# Battery.net
KiCad netlist of a schematic drawn in Altium Designer
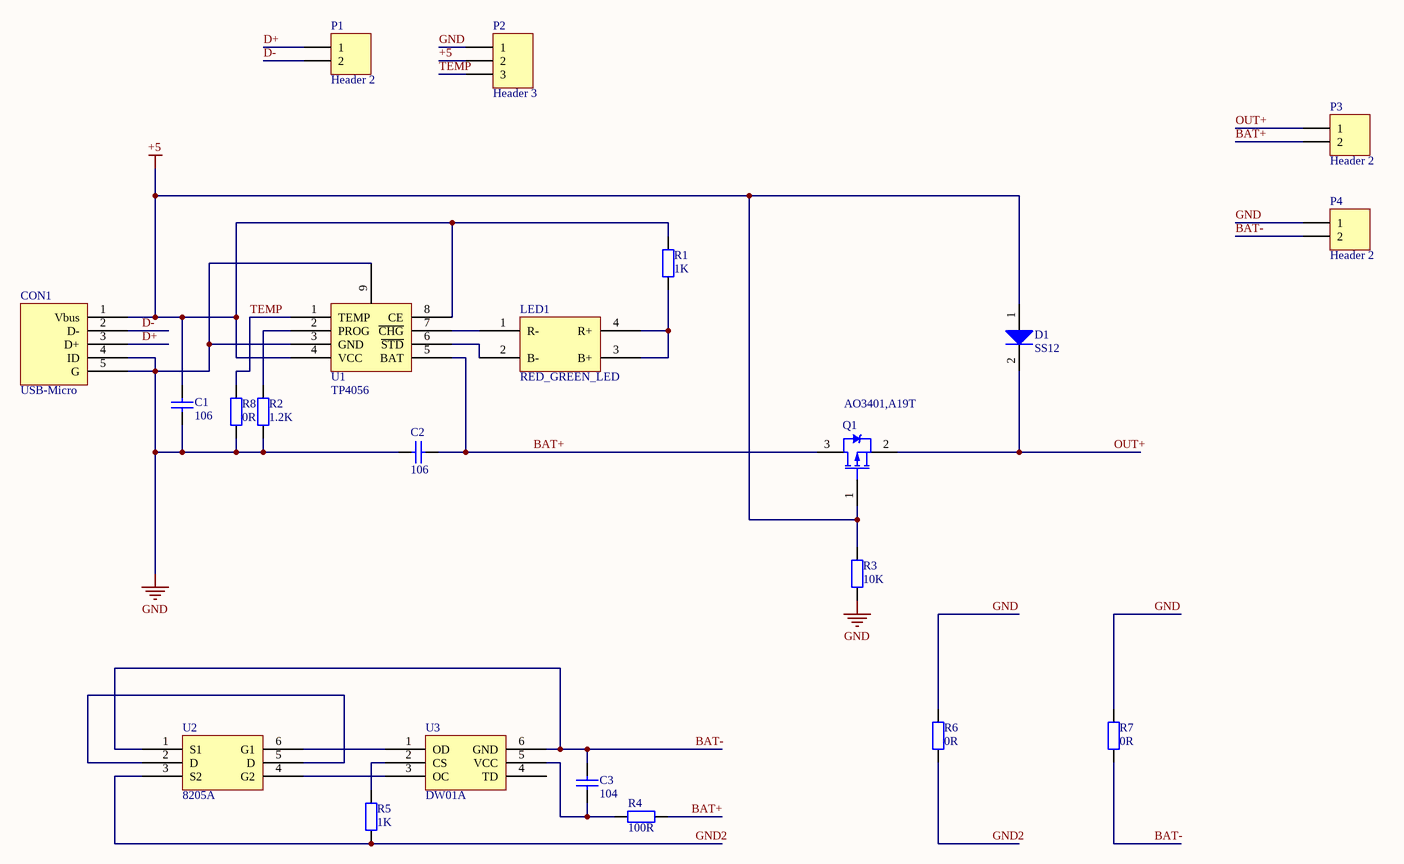
[diagram p0: Battery.SchDoc]

(export (version "E")
  (design (tool "Eeschema 10.0.6"))
  (components
    (comp (ref "C1")
      (value "106")
      (footprint "Battery:CAPC1608L")
      (description "Capacitor")
      (fields (field (name "Comment") "Cap") (field (name "PUBLISHER") "Altium Limited"))
      (libsource (lib "Miscellaneous Devices") (part "Cap"))
    )
    (comp (ref "C2")
      (value "106")
      (footprint "Battery:CAPC1608L")
      (description "Capacitor")
      (fields (field (name "Comment") "Cap") (field (name "PUBLISHER") "Altium Limited"))
      (libsource (lib "Miscellaneous Devices") (part "Cap"))
    )
    (comp (ref "C3")
      (value "104")
      (footprint "Battery:CAPC1608L")
      (description "Capacitor")
      (fields (field (name "Comment") "Cap") (field (name "PUBLISHER") "Altium Limited"))
      (libsource (lib "Miscellaneous Devices") (part "Cap"))
    )
    (comp (ref "CON1")
      (value "USB-Micro")
      (footprint "Battery:USB-micro_B")
      (libsource (lib "Battery") (part "USB-Micro"))
    )
    (comp (ref "D1")
      (value "SS12")
      (footprint "Battery:DO-214AC")
      (description "1N4148")
      (fields (field (name "PUBLISHER") "Altium Limited"))
      (libsource (lib "Miscellaneous Devices") (part "Diode"))
    )
    (comp (ref "LED1")
      (value "RED_GREEN_LED")
      (footprint "Battery:RED_GREEN_LED1206")
      (libsource (lib "Battery") (part "RED_GREEN_LED"))
    )
    (comp (ref "P1")
      (value "Header 2")
      (footprint "HDR1X2")
      (description "Header, 2-Pin")
      (fields (field (name "PUBLISHER") "Altium Limited"))
      (libsource (lib "Miscellaneous Connectors") (part "Header 2"))
    )
    (comp (ref "P2")
      (value "Header 3")
      (footprint "HDR1X3")
      (description "Header, 3-Pin")
      (fields (field (name "PUBLISHER") "Altium Limited"))
      (libsource (lib "Miscellaneous Connectors") (part "Header 3"))
    )
    (comp (ref "P3")
      (value "Header 2")
      (footprint "HDR1X2")
      (description "Header, 2-Pin")
      (fields (field (name "PUBLISHER") "Altium Limited"))
      (libsource (lib "Miscellaneous Connectors") (part "Header 2"))
    )
    (comp (ref "P4")
      (value "Header 2")
      (footprint "HDR1X2")
      (description "Header, 2-Pin")
      (fields (field (name "PUBLISHER") "Altium Limited"))
      (libsource (lib "Miscellaneous Connectors") (part "Header 2"))
    )
    (comp (ref "Q1")
      (value "AO3401,A19T")
      (footprint "Battery:SOT-23B_L")
      (description "P-Channel Power MOSFET")
      (fields (field (name "PUBLISHER") "Altium Limited"))
      (libsource (lib "Miscellaneous Devices") (part "PMOS-2"))
    )
    (comp (ref "R1")
      (value "1K")
      (footprint "Battery:RESC1608L")
      (description "Resistor")
      (fields (field (name "Comment") "Res2") (field (name "PUBLISHER") "Altium Limited"))
      (libsource (lib "Miscellaneous Devices") (part "Res2"))
    )
    (comp (ref "R2")
      (value "1.2K")
      (footprint "Battery:RESC1608L")
      (description "Resistor")
      (fields (field (name "Comment") "Res2") (field (name "PUBLISHER") "Altium Limited"))
      (libsource (lib "Miscellaneous Devices") (part "Res2"))
    )
    (comp (ref "R3")
      (value "10K")
      (footprint "Battery:RESC1608L")
      (description "Resistor")
      (fields (field (name "Comment") "Res2") (field (name "PUBLISHER") "Altium Limited"))
      (libsource (lib "Miscellaneous Devices") (part "Res2"))
    )
    (comp (ref "R4")
      (value "100R")
      (footprint "Battery:RESC1608L")
      (description "Resistor")
      (fields (field (name "Comment") "Res2") (field (name "PUBLISHER") "Altium Limited"))
      (libsource (lib "") (part "Res2_1"))
    )
    (comp (ref "R5")
      (value "1K")
      (footprint "Battery:RESC1608L")
      (description "Resistor")
      (fields (field (name "Comment") "Res2") (field (name "PUBLISHER") "Altium Limited"))
      (libsource (lib "Miscellaneous Devices") (part "Res2"))
    )
    (comp (ref "R6")
      (value "0R")
      (footprint "Battery:RESC1608L")
      (description "Resistor")
      (fields (field (name "Comment") "Res2") (field (name "PUBLISHER") "Altium Limited"))
      (libsource (lib "Miscellaneous Devices") (part "Res2"))
    )
    (comp (ref "R7")
      (value "0R")
      (footprint "Battery:RESC1608L")
      (description "Resistor")
      (fields (field (name "Comment") "Res2") (field (name "PUBLISHER") "Altium Limited"))
      (libsource (lib "Miscellaneous Devices") (part "Res2"))
    )
    (comp (ref "R8")
      (value "0R")
      (footprint "Battery:RESC1608L")
      (description "Resistor")
      (fields (field (name "Comment") "Res2") (field (name "PUBLISHER") "Altium Limited"))
      (libsource (lib "Miscellaneous Devices") (part "Res2"))
    )
    (comp (ref "U1")
      (value "TP4056")
      (footprint "Battery:SOP127P780-8M")
      (libsource (lib "Battery") (part "TP4056"))
    )
    (comp (ref "U2")
      (value "8205A")
      (footprint "Battery:SOT95P330-6M")
      (libsource (lib "Battery") (part "8205A"))
    )
    (comp (ref "U3")
      (value "DW01A")
      (footprint "Battery:SOT95P330-6M")
      (libsource (lib "Battery") (part "DW01A"))
    )
  )
  (nets
    (net (code "1") (name "+5") (class "Default")
      (node (ref "C1") (pin "2") (pinfunction "2_2") (pintype "passive"))
      (node (ref "CON1") (pin "1") (pinfunction "Vbus_1") (pintype "passive"))
      (node (ref "D1") (pin "1") (pinfunction "A_1") (pintype "passive"))
      (node (ref "P2") (pin "2") (pinfunction "2_2") (pintype "passive"))
      (node (ref "Q1") (pin "1") (pinfunction "G_1") (pintype "passive"))
      (node (ref "R1") (pin "2") (pinfunction "2_2") (pintype "passive"))
      (node (ref "R3") (pin "2") (pinfunction "2_2") (pintype "passive"))
      (node (ref "U1") (pin "4") (pinfunction "VCC_4") (pintype "passive"))
      (node (ref "U1") (pin "8") (pinfunction "CE_8") (pintype "passive"))
    )
    (net (code "2") (name "/BAT+") (class "Default")
      (node (ref "C2") (pin "1") (pinfunction "1_1") (pintype "passive"))
      (node (ref "P3") (pin "2") (pinfunction "2_2") (pintype "passive"))
      (node (ref "Q1") (pin "3") (pinfunction "D_3") (pintype "passive"))
      (node (ref "R4") (pin "1") (pinfunction "1_1") (pintype "passive"))
      (node (ref "U1") (pin "5") (pinfunction "BAT_5") (pintype "passive"))
    )
    (net (code "3") (name "/BAT-") (class "Default")
      (node (ref "C3") (pin "1") (pinfunction "1_1") (pintype "passive"))
      (node (ref "P4") (pin "2") (pinfunction "2_2") (pintype "passive"))
      (node (ref "R7") (pin "1") (pinfunction "1_1") (pintype "passive"))
      (node (ref "U2") (pin "1") (pinfunction "S1_1") (pintype "passive"))
      (node (ref "U3") (pin "6") (pinfunction "GND_6") (pintype "passive"))
    )
    (net (code "4") (name "/D+") (class "Default")
      (node (ref "CON1") (pin "3") (pinfunction "D+_3") (pintype "passive"))
      (node (ref "P1") (pin "1") (pinfunction "1_1") (pintype "passive"))
    )
    (net (code "5") (name "/D-") (class "Default")
      (node (ref "CON1") (pin "2") (pinfunction "D-_2") (pintype "passive"))
      (node (ref "P1") (pin "2") (pinfunction "2_2") (pintype "passive"))
    )
    (net (code "6") (name "/GND2") (class "Default")
      (node (ref "R5") (pin "1") (pinfunction "1_1") (pintype "passive"))
      (node (ref "R6") (pin "1") (pinfunction "1_1") (pintype "passive"))
      (node (ref "U2") (pin "3") (pinfunction "S2_3") (pintype "passive"))
    )
    (net (code "7") (name "/OUT+") (class "Default")
      (node (ref "D1") (pin "2") (pinfunction "K_2") (pintype "passive"))
      (node (ref "P3") (pin "1") (pinfunction "1_1") (pintype "passive"))
      (node (ref "Q1") (pin "2") (pinfunction "S_2") (pintype "passive"))
    )
    (net (code "8") (name "/TEMP") (class "Default")
      (node (ref "P2") (pin "3") (pinfunction "3_3") (pintype "passive"))
      (node (ref "R8") (pin "2") (pinfunction "2_2") (pintype "passive"))
      (node (ref "U1") (pin "1") (pinfunction "TEMP_1") (pintype "passive"))
    )
    (net (code "9") (name "GND") (class "Default")
      (node (ref "C1") (pin "1") (pinfunction "1_1") (pintype "passive"))
      (node (ref "C2") (pin "2") (pinfunction "2_2") (pintype "passive"))
      (node (ref "CON1") (pin "4") (pinfunction "ID_4") (pintype "passive"))
      (node (ref "CON1") (pin "5") (pinfunction "G_5") (pintype "passive"))
      (node (ref "P2") (pin "1") (pinfunction "1_1") (pintype "passive"))
      (node (ref "P4") (pin "1") (pinfunction "1_1") (pintype "passive"))
      (node (ref "R2") (pin "1") (pinfunction "1_1") (pintype "passive"))
      (node (ref "R3") (pin "1") (pinfunction "1_1") (pintype "passive"))
      (node (ref "R6") (pin "2") (pinfunction "2_2") (pintype "passive"))
      (node (ref "R7") (pin "2") (pinfunction "2_2") (pintype "passive"))
      (node (ref "R8") (pin "1") (pinfunction "1_1") (pintype "passive"))
      (node (ref "U1") (pin "3") (pinfunction "GND_3") (pintype "passive"))
      (node (ref "U1") (pin "9") (pinfunction "9_9") (pintype "passive"))
    )
    (net (code "10") (name "Net-(LED1-B+)") (class "Default")
      (node (ref "LED1") (pin "3") (pinfunction "B+_3") (pintype "passive"))
      (node (ref "LED1") (pin "4") (pinfunction "R+_4") (pintype "passive"))
      (node (ref "R1") (pin "1") (pinfunction "1_1") (pintype "passive"))
    )
    (net (code "11") (name "Net-(LED1-B-)") (class "Default")
      (node (ref "LED1") (pin "2") (pinfunction "B-_2") (pintype "passive"))
      (node (ref "U1") (pin "6") (pinfunction "~{STD}_6") (pintype "passive"))
    )
    (net (code "12") (name "Net-(LED1-R-)") (class "Default")
      (node (ref "LED1") (pin "1") (pinfunction "R-_1") (pintype "passive"))
      (node (ref "U1") (pin "7") (pinfunction "~{CHG}_7") (pintype "passive"))
    )
    (net (code "13") (name "Net-(U1-PROG)") (class "Default")
      (node (ref "R2") (pin "2") (pinfunction "2_2") (pintype "passive"))
      (node (ref "U1") (pin "2") (pinfunction "PROG_2") (pintype "passive"))
    )
    (net (code "14") (name "Net-(U2-D-Pad2)") (class "Default")
      (node (ref "U2") (pin "2") (pinfunction "D_2") (pintype "passive"))
      (node (ref "U2") (pin "5") (pinfunction "D_5") (pintype "passive"))
    )
    (net (code "15") (name "Net-(U2-G1)") (class "Default")
      (node (ref "U2") (pin "6") (pinfunction "G1_6") (pintype "passive"))
      (node (ref "U3") (pin "1") (pinfunction "OD_1") (pintype "passive"))
    )
    (net (code "16") (name "Net-(U2-G2)") (class "Default")
      (node (ref "U2") (pin "4") (pinfunction "G2_4") (pintype "passive"))
      (node (ref "U3") (pin "3") (pinfunction "OC_3") (pintype "passive"))
    )
    (net (code "17") (name "Net-(U3-CS)") (class "Default")
      (node (ref "R5") (pin "2") (pinfunction "2_2") (pintype "passive"))
      (node (ref "U3") (pin "2") (pinfunction "CS_2") (pintype "passive"))
    )
    (net (code "18") (name "Net-(U3-VCC)") (class "Default")
      (node (ref "C3") (pin "2") (pinfunction "2_2") (pintype "passive"))
      (node (ref "R4") (pin "2") (pinfunction "2_2") (pintype "passive"))
      (node (ref "U3") (pin "5") (pinfunction "VCC_5") (pintype "passive"))
    )
    (net (code "19") (name "unconnected-(U3-TD-Pad4)") (class "Default")
      (node (ref "U3") (pin "4") (pinfunction "TD_4") (pintype "passive"))
    )
  )
)
